# SCH_miliohn_2026-04-19.net
KiCad netlist of a schematic drawn in EasyEDA
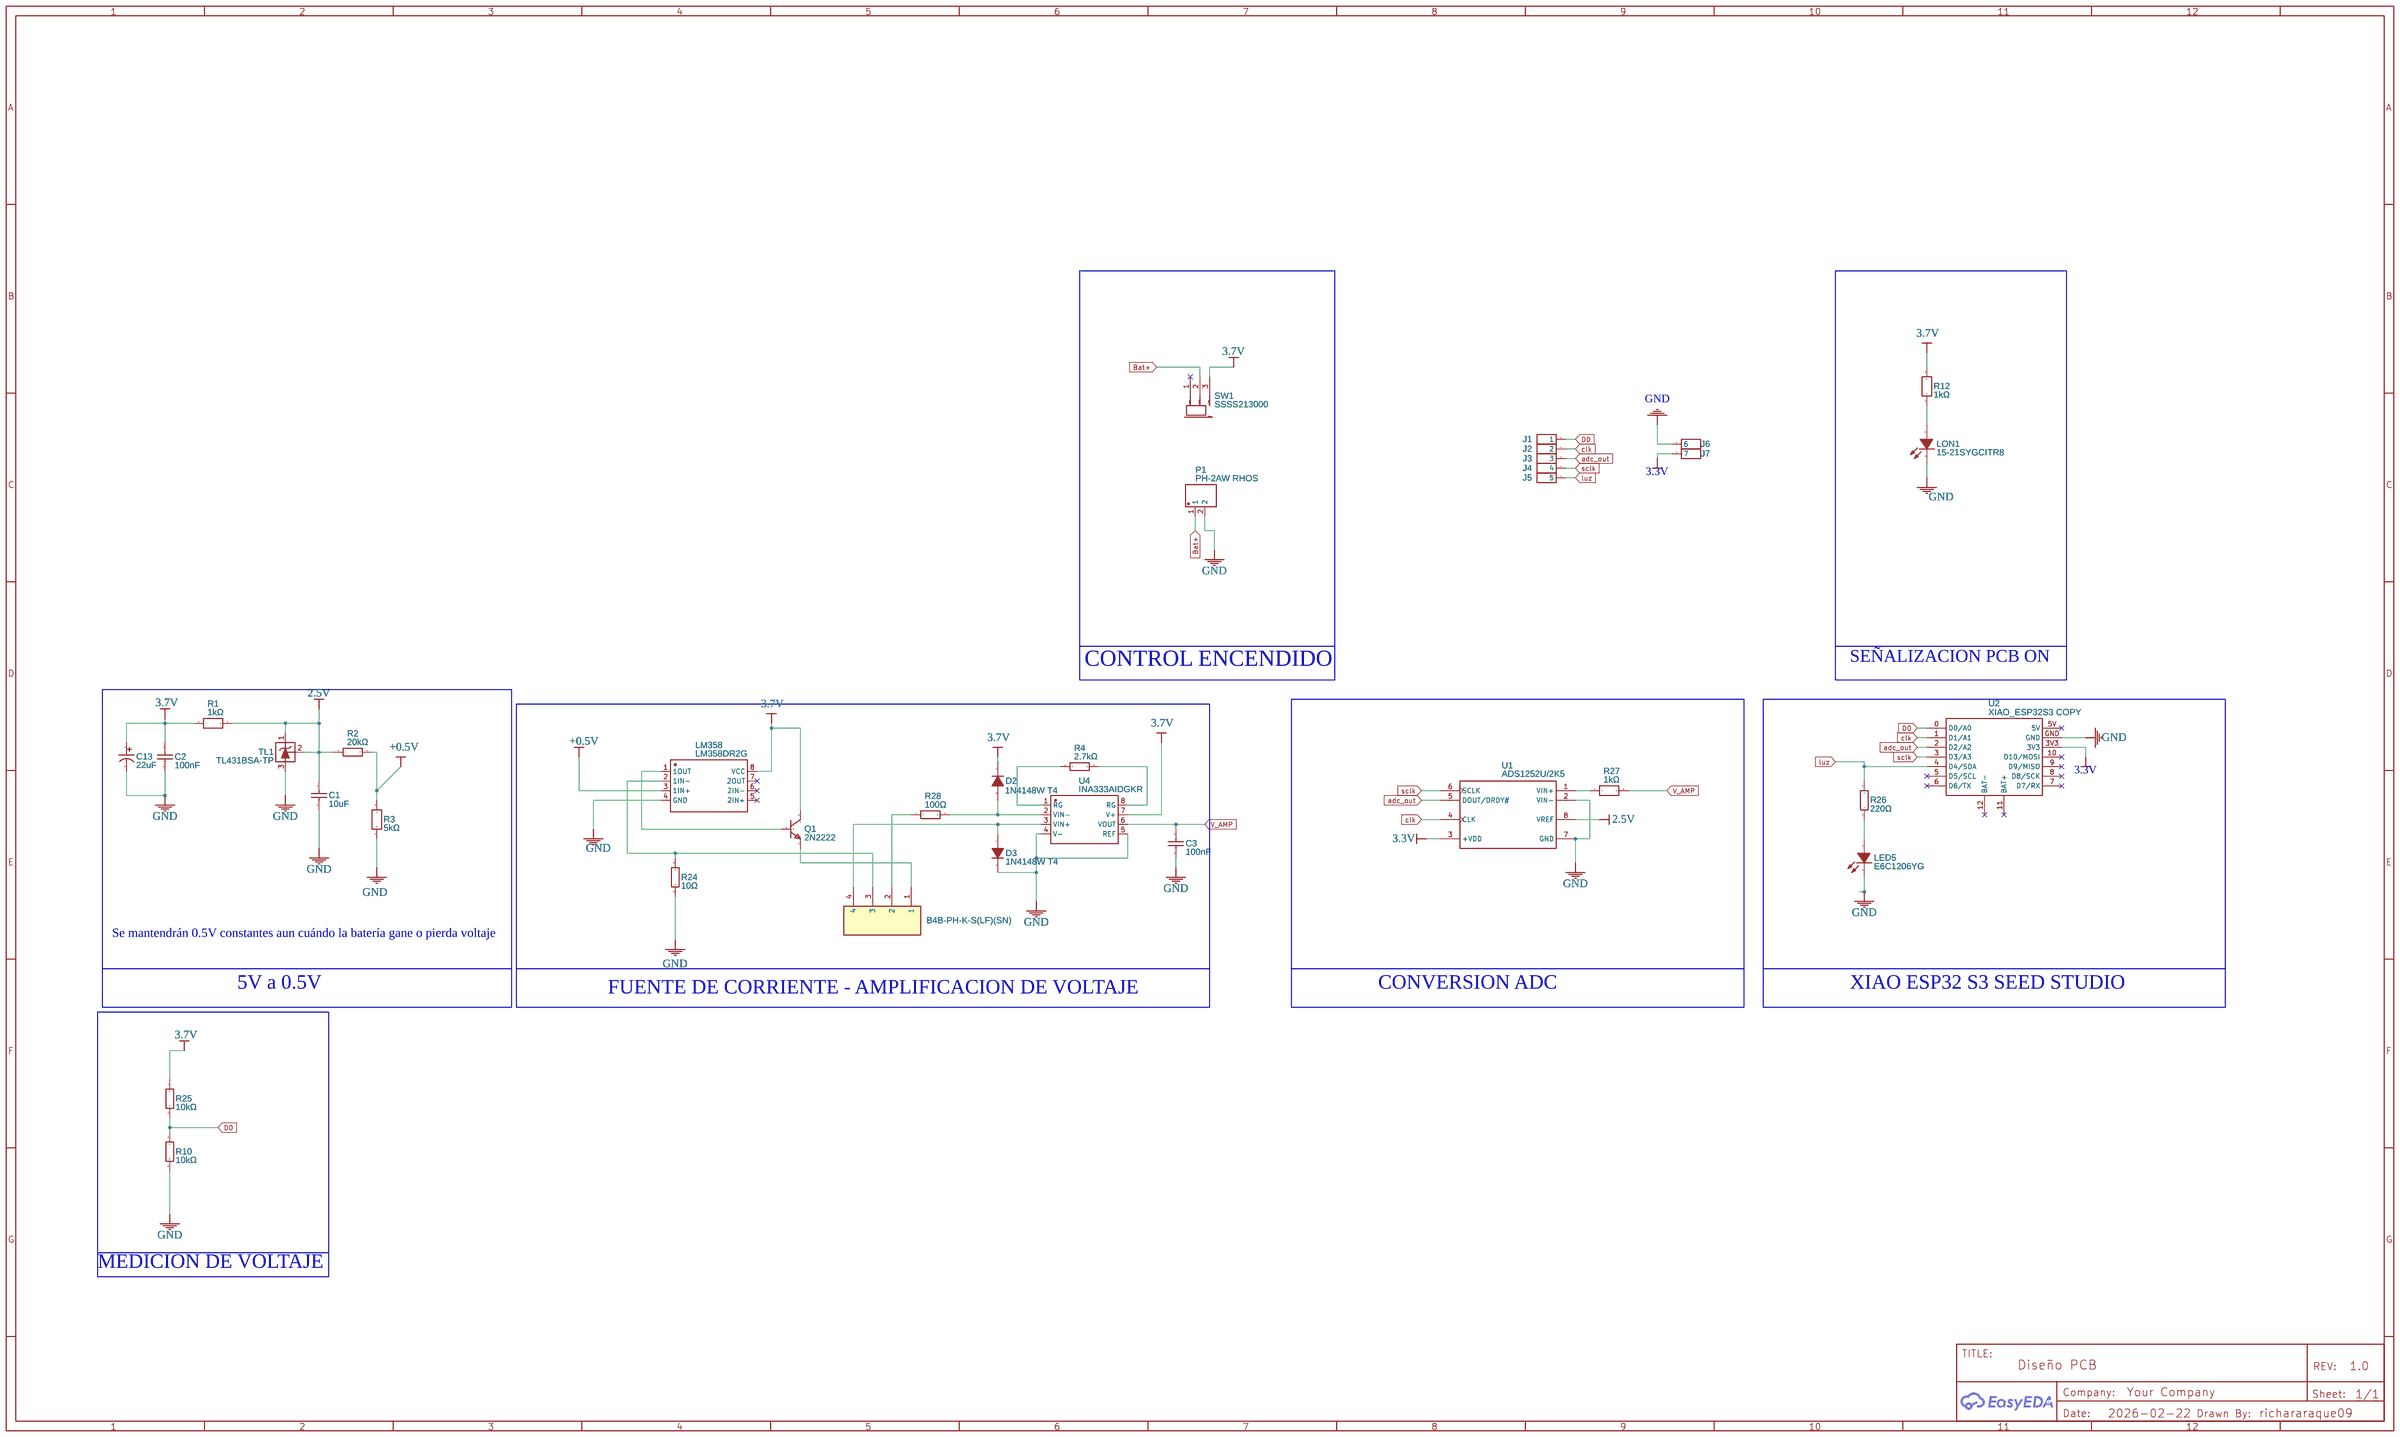
[diagram p0: schematic sheet]

(export (version "E")
  (design (tool "Eeschema 10.0.6"))
  (components
    (comp (ref "C1")
      (value "10uF")
      (fields
        (field (name "Manufacturer Part") "CL31A106KBHNNNE")
        (field (name "Manufacturer") "SAMSUNG(三星)")
      )
      (libsource (lib "") (part "CL31A106KBHNNNE"))
    )
    (comp (ref "C2")
      (value "100nF")
      (fields
        (field (name "Manufacturer Part") "CL31B104KBCNNNC")
        (field (name "Manufacturer") "SAMSUNG(三星)")
      )
      (libsource (lib "") (part "CL31B104KBCNNNC"))
    )
    (comp (ref "C3")
      (value "100nF")
      (fields
        (field (name "Manufacturer Part") "CL31B104KBCNNNC")
        (field (name "Manufacturer") "SAMSUNG(三星)")
      )
      (libsource (lib "") (part "CL31B104KBCNNNC"))
    )
    (comp (ref "C13")
      (value "22uF")
      (fields (field (name "Manufacturer Part") "RVT1C220M0405") (field (name "Manufacturer") "HONOR(荣誉)"))
      (libsource (lib "") (part "RVT1C220M0405_C3356"))
    )
    (comp (ref "D2")
      (value "1N4148W T4")
      (fields (field (name "Manufacturer Part") "1N4148W") (field (name "Manufacturer") "CJ(江苏长电/长晶)"))
      (libsource (lib "") (part "1N4148W T4"))
    )
    (comp (ref "D3")
      (value "1N4148W T4")
      (fields (field (name "Manufacturer Part") "1N4148W") (field (name "Manufacturer") "CJ(江苏长电/长晶)"))
      (libsource (lib "") (part "1N4148W T4_1"))
    )
    (comp (ref "J1") (value "HDR-M-2.54_1x1") (libsource (lib "") (part "HDR-M-2.54_1x1_4")))
    (comp (ref "J2") (value "HDR-M-2.54_1x1") (libsource (lib "") (part "HDR-M-2.54_1x1_3")))
    (comp (ref "J3") (value "HDR-M-2.54_1x1") (libsource (lib "") (part "HDR-M-2.54_1x1_2")))
    (comp (ref "J4") (value "HDR-M-2.54_1x1") (libsource (lib "") (part "HDR-M-2.54_1x1_5")))
    (comp (ref "J5") (value "HDR-M-2.54_1x1") (libsource (lib "") (part "HDR-M-2.54_1x1_1")))
    (comp (ref "J6") (value "HDR-M-2.54_1x1") (libsource (lib "") (part "HDR-M-2.54_1x1_6")))
    (comp (ref "J7") (value "HDR-M-2.54_1x1") (libsource (lib "") (part "HDR-M-2.54_1x1")))
    (comp (ref "LED5")
      (value "E6C1206YG")
      (fields (field (name "Manufacturer Part") "KT-1206YG") (field (name "Manufacturer") "KENTO"))
      (libsource (lib "") (part "E6C1206YG"))
    )
    (comp (ref "LM358")
      (value "LM358DR2G")
      (fields (field (name "Manufacturer") "onsemi(安森美)"))
      (libsource (lib "") (part "LM358DR2G"))
    )
    (comp (ref "LON1")
      (value "15-21SYGCITR8")
      (fields (field (name "Manufacturer Part") "KT-1206Y") (field (name "Manufacturer") "KENTO"))
      (libsource (lib "") (part "15-21SYGCITR8"))
    )
    (comp (ref "P1")
      (value "PH-2AW RHOS")
      (fields (field (name "Manufacturer Part") "PH-2AW") (field (name "Manufacturer") "BOOMELE(博穆精密)"))
      (libsource (lib "") (part "PH-2AW RHOS"))
    )
    (comp (ref "Q1")
      (value "2N2222")
      (fields (field (name "Manufacturer Part") "2N2222A") (field (name "Manufacturer") "ST(先科)"))
      (libsource (lib "") (part "2N2222"))
    )
    (comp (ref "R1")
      (value "1kΩ")
      (fields (field (name "Manufacturer Part") "SCR1206J1K") (field (name "Manufacturer") "VO(翔胜)"))
      (libsource (lib "") (part "SCR1206J1K"))
    )
    (comp (ref "R2")
      (value "20kΩ")
      (fields
        (field (name "Manufacturer Part") "1206W4F2002T5E")
        (field (name "Manufacturer") "UNI-ROYAL(厚声)")
      )
      (libsource (lib "") (part "1206W4F2002T5E"))
    )
    (comp (ref "R3")
      (value "5kΩ")
      (fields (field (name "Manufacturer Part") "RT1206BRD075KL") (field (name "Manufacturer") "YAGEO(国巨)"))
      (libsource (lib "") (part "RT1206BRD075KL"))
    )
    (comp (ref "R4")
      (value "2.7kΩ")
      (fields
        (field (name "Manufacturer Part") "1206W4F2701T5E")
        (field (name "Manufacturer") "UNI-ROYAL(厚声)")
      )
      (libsource (lib "") (part "1206W4F2701T5E"))
    )
    (comp (ref "R10")
      (value "10kΩ")
      (fields
        (field (name "Manufacturer Part") "1206W4F1002T5E")
        (field (name "Manufacturer") "UNI-ROYAL(厚声)")
      )
      (libsource (lib "") (part "1206W4F1002T5E"))
    )
    (comp (ref "R12")
      (value "1kΩ")
      (fields (field (name "Manufacturer Part") "SCR1206J1K") (field (name "Manufacturer") "VO(翔胜)"))
      (libsource (lib "") (part "SCR1206J1K_1"))
    )
    (comp (ref "R24")
      (value "10Ω")
      (fields (field (name "Manufacturer Part") "SG732BTTD100K") (field (name "Manufacturer") "KOA"))
      (libsource (lib "") (part "SG732BTTD100K"))
    )
    (comp (ref "R25")
      (value "10kΩ")
      (fields
        (field (name "Manufacturer Part") "1206W4F1002T5E")
        (field (name "Manufacturer") "UNI-ROYAL(厚声)")
      )
      (libsource (lib "") (part "1206W4F1002T5E"))
    )
    (comp (ref "R26")
      (value "220Ω")
      (fields
        (field (name "Manufacturer Part") "1206W4F2200T5E")
        (field (name "Manufacturer") "UNI-ROYAL(厚声)")
      )
      (libsource (lib "") (part "1206W4F2200T5E"))
    )
    (comp (ref "R27")
      (value "1kΩ")
      (fields (field (name "Manufacturer Part") "SCR1206J1K") (field (name "Manufacturer") "VO(翔胜)"))
      (libsource (lib "") (part "SCR1206J1K"))
    )
    (comp (ref "R28")
      (value "100Ω")
      (fields
        (field (name "Manufacturer Part") "0805W8F1000T5E")
        (field (name "Manufacturer") "UNI-ROYAL(厚声)")
      )
      (libsource (lib "") (part "0805W8F1000T5E"))
    )
    (comp (ref "SW1")
      (value "SSSS213000")
      (fields (field (name "Manufacturer") "ALPSALPINE(阿尔卑斯阿尔派)"))
      (libsource (lib "") (part "SSSS213000"))
    )
    (comp (ref "TEST1")
      (value "B4B-PH-K-S(LF)(SN)")
      (fields (field (name "Manufacturer") "JST"))
      (libsource (lib "") (part "B4B-PH-K-S(LF)(SN)"))
    )
    (comp (ref "TL1")
      (value "TL431BSA-TP")
      (fields (field (name "Manufacturer") "TECH PUBLIC(台舟)"))
      (libsource (lib "") (part "TL431BSA-TP"))
    )
    (comp (ref "U1")
      (value "ADS1252U/2K5")
      (fields (field (name "Manufacturer") "TI(德州仪器)"))
      (libsource (lib "") (part "ADS1252U/2K5"))
    )
    (comp (ref "U2")
      (value "XIAO_ESP32S3 COPY")
      (fields (field (name "Manufacturer Part") "XIAO ESP32S3") (field (name "Manufacturer") "SeeedStudio"))
      (libsource (lib "") (part "XIAO_ESP32S3 COPY"))
    )
    (comp (ref "U4")
      (value "INA333AIDGKR")
      (fields (field (name "Manufacturer") "TI(德州仪器)"))
      (libsource (lib "") (part "INA333AIDGKR"))
    )
  )
  (nets
    (net (code "1") (name "+0.5V") (class "Default")
      (node (ref "LM358") (pin "3") (pinfunction "1IN+_3") (pintype "unspecified"))
      (node (ref "R2") (pin "1") (pinfunction "1_1") (pintype "input"))
      (node (ref "R3") (pin "2") (pinfunction "2_2") (pintype "unspecified"))
    )
    (net (code "2") (name "2.5V") (class "Default")
      (node (ref "C1") (pin "1") (pinfunction "1_1") (pintype "input"))
      (node (ref "R1") (pin "2") (pinfunction "2_2") (pintype "unspecified"))
      (node (ref "R2") (pin "2") (pinfunction "2_2") (pintype "input"))
      (node (ref "TL1") (pin "1") (pinfunction "K_1") (pintype "unspecified"))
      (node (ref "TL1") (pin "2") (pinfunction "REF_2") (pintype "unspecified"))
      (node (ref "U1") (pin "8") (pinfunction "VREF_8") (pintype "unspecified"))
    )
    (net (code "3") (name "3.3V") (class "Default")
      (node (ref "J7") (pin "1") (pinfunction "7_1") (pintype "input"))
      (node (ref "U1") (pin "3") (pinfunction "+VDD_3") (pintype "passive"))
      (node (ref "U2") (pin "3V3") (pinfunction "3V3_3V3") (pintype "unspecified"))
    )
    (net (code "4") (name "3.7V") (class "Default")
      (node (ref "C13") (pin "1") (pinfunction "1_1") (pintype "input"))
      (node (ref "C2") (pin "1") (pinfunction "1_1") (pintype "input"))
      (node (ref "D2") (pin "1") (pinfunction "K_1") (pintype "unspecified"))
      (node (ref "LM358") (pin "8") (pinfunction "VCC_8") (pintype "unspecified"))
      (node (ref "Q1") (pin "3") (pinfunction "C_3") (pintype "unspecified"))
      (node (ref "R1") (pin "1") (pinfunction "1_1") (pintype "unspecified"))
      (node (ref "R12") (pin "2") (pinfunction "2_2") (pintype "unspecified"))
      (node (ref "R25") (pin "1") (pinfunction "1_1") (pintype "input"))
      (node (ref "SW1") (pin "3") (pinfunction "3_3") (pintype "unspecified"))
      (node (ref "U4") (pin "7") (pinfunction "V+_7") (pintype "unspecified"))
    )
    (net (code "5") (name "Bat+") (class "Default")
      (node (ref "P1") (pin "1") (pinfunction "1_1") (pintype "unspecified"))
      (node (ref "SW1") (pin "2") (pinfunction "2_2") (pintype "unspecified"))
    )
    (net (code "6") (name "D0") (class "Default")
      (node (ref "J1") (pin "1") (pinfunction "1_1") (pintype "input"))
      (node (ref "R10") (pin "1") (pinfunction "1_1") (pintype "input"))
      (node (ref "R25") (pin "2") (pinfunction "2_2") (pintype "input"))
      (node (ref "U2") (pin "0") (pinfunction "D0/A0_0") (pintype "unspecified"))
    )
    (net (code "7") (name "GND") (class "Default")
      (node (ref "C1") (pin "2") (pinfunction "2_2") (pintype "input"))
      (node (ref "C13") (pin "2") (pinfunction "2_2") (pintype "input"))
      (node (ref "C2") (pin "2") (pinfunction "2_2") (pintype "input"))
      (node (ref "C3") (pin "2") (pinfunction "2_2") (pintype "input"))
      (node (ref "D3") (pin "1") (pinfunction "K_1") (pintype "unspecified"))
      (node (ref "J6") (pin "1") (pinfunction "6_1") (pintype "input"))
      (node (ref "LED5") (pin "2") (pinfunction "-_2") (pintype "unspecified"))
      (node (ref "LM358") (pin "4") (pinfunction "GND_4") (pintype "unspecified"))
      (node (ref "LON1") (pin "1") (pinfunction "-_1") (pintype "unspecified"))
      (node (ref "P1") (pin "2") (pinfunction "2_2") (pintype "unspecified"))
      (node (ref "R10") (pin "2") (pinfunction "2_2") (pintype "input"))
      (node (ref "R24") (pin "1") (pinfunction "1_1") (pintype "unspecified"))
      (node (ref "R3") (pin "1") (pinfunction "1_1") (pintype "unspecified"))
      (node (ref "TL1") (pin "3") (pinfunction "A_3") (pintype "unspecified"))
      (node (ref "U1") (pin "2") (pinfunction "VIN-_2") (pintype "unspecified"))
      (node (ref "U1") (pin "7") (pinfunction "GND_7") (pintype "passive"))
      (node (ref "U2") (pin "GND") (pinfunction "GND_GND") (pintype "unspecified"))
      (node (ref "U4") (pin "4") (pinfunction "V-_4") (pintype "unspecified"))
      (node (ref "U4") (pin "5") (pinfunction "REF_5") (pintype "unspecified"))
    )
    (net (code "8") (name "Net-(D2-A)") (class "Default")
      (node (ref "D2") (pin "2") (pinfunction "A_2") (pintype "unspecified"))
      (node (ref "R28") (pin "2") (pinfunction "2_2") (pintype "input"))
      (node (ref "U4") (pin "2") (pinfunction "VIN-_2") (pintype "unspecified"))
    )
    (net (code "9") (name "Net-(D3-A)") (class "Default")
      (node (ref "D3") (pin "2") (pinfunction "A_2") (pintype "unspecified"))
      (node (ref "TEST1") (pin "4") (pinfunction "4_4") (pintype "input"))
      (node (ref "U4") (pin "3") (pinfunction "VIN+_3") (pintype "unspecified"))
    )
    (net (code "10") (name "Net-(LED5-+)") (class "Default")
      (node (ref "LED5") (pin "1") (pinfunction "+_1") (pintype "unspecified"))
      (node (ref "R26") (pin "1") (pinfunction "1_1") (pintype "input"))
    )
    (net (code "11") (name "Net-(LM358-1IN-)") (class "Default")
      (node (ref "LM358") (pin "2") (pinfunction "1IN-_2") (pintype "unspecified"))
      (node (ref "R24") (pin "2") (pinfunction "2_2") (pintype "unspecified"))
      (node (ref "TEST1") (pin "3") (pinfunction "3_3") (pintype "input"))
    )
    (net (code "12") (name "Net-(LM358-1OUT)") (class "Default")
      (node (ref "LM358") (pin "1") (pinfunction "1OUT_1") (pintype "unspecified"))
      (node (ref "Q1") (pin "2") (pinfunction "B_2") (pintype "unspecified"))
    )
    (net (code "13") (name "Net-(LON1-+)") (class "Default")
      (node (ref "LON1") (pin "2") (pinfunction "+_2") (pintype "unspecified"))
      (node (ref "R12") (pin "1") (pinfunction "1_1") (pintype "unspecified"))
    )
    (net (code "14") (name "Net-(Q1-E)") (class "Default")
      (node (ref "Q1") (pin "1") (pinfunction "E_1") (pintype "unspecified"))
      (node (ref "TEST1") (pin "1") (pinfunction "1_1") (pintype "input"))
    )
    (net (code "15") (name "Net-(R4-Pad1)") (class "Default")
      (node (ref "R4") (pin "1") (pinfunction "1_1") (pintype "input"))
      (node (ref "U4") (pin "1") (pinfunction "RG_1") (pintype "unspecified"))
    )
    (net (code "16") (name "Net-(R4-Pad2)") (class "Default")
      (node (ref "R4") (pin "2") (pinfunction "2_2") (pintype "input"))
      (node (ref "U4") (pin "8") (pinfunction "RG_8") (pintype "unspecified"))
    )
    (net (code "17") (name "Net-(R28-Pad1)") (class "Default")
      (node (ref "R28") (pin "1") (pinfunction "1_1") (pintype "input"))
      (node (ref "TEST1") (pin "2") (pinfunction "2_2") (pintype "input"))
    )
    (net (code "18") (name "Net-(U1-VIN+)") (class "Default")
      (node (ref "R27") (pin "1") (pinfunction "1_1") (pintype "unspecified"))
      (node (ref "U1") (pin "1") (pinfunction "VIN+_1") (pintype "unspecified"))
    )
    (net (code "19") (name "V_AMP") (class "Default")
      (node (ref "C3") (pin "1") (pinfunction "1_1") (pintype "input"))
      (node (ref "R27") (pin "2") (pinfunction "2_2") (pintype "unspecified"))
      (node (ref "U4") (pin "6") (pinfunction "VOUT_6") (pintype "unspecified"))
    )
    (net (code "20") (name "adc_out") (class "Default")
      (node (ref "J3") (pin "1") (pinfunction "3_1") (pintype "input"))
      (node (ref "U1") (pin "5") (pinfunction "DOUT/DRDY#_5") (pintype "output"))
      (node (ref "U2") (pin "2") (pinfunction "D2/A2_2") (pintype "unspecified"))
    )
    (net (code "21") (name "clk") (class "Default")
      (node (ref "J2") (pin "1") (pinfunction "2_1") (pintype "input"))
      (node (ref "U1") (pin "4") (pinfunction "CLK_4") (pintype "unspecified"))
      (node (ref "U2") (pin "1") (pinfunction "D1/A1_1") (pintype "unspecified"))
    )
    (net (code "22") (name "luz") (class "Default")
      (node (ref "J5") (pin "1") (pinfunction "5_1") (pintype "input"))
      (node (ref "R26") (pin "2") (pinfunction "2_2") (pintype "input"))
      (node (ref "U2") (pin "4") (pinfunction "D4/SDA_4") (pintype "unspecified"))
    )
    (net (code "23") (name "sclk") (class "Default")
      (node (ref "J4") (pin "1") (pinfunction "4_1") (pintype "input"))
      (node (ref "U1") (pin "6") (pinfunction "SCLK_6") (pintype "unspecified"))
      (node (ref "U2") (pin "3") (pinfunction "D3/A3_3") (pintype "unspecified"))
    )
    (net (code "24") (name "unconnected-(LM358-2IN+-Pad5)") (class "Default")
      (node (ref "LM358") (pin "5") (pinfunction "2IN+_5") (pintype "unspecified+no_connect"))
    )
    (net (code "25") (name "unconnected-(LM358-2IN--Pad6)") (class "Default")
      (node (ref "LM358") (pin "6") (pinfunction "2IN-_6") (pintype "unspecified+no_connect"))
    )
    (net (code "26") (name "unconnected-(LM358-2OUT-Pad7)") (class "Default")
      (node (ref "LM358") (pin "7") (pinfunction "2OUT_7") (pintype "unspecified+no_connect"))
    )
    (net (code "27") (name "unconnected-(SW1-Pad1)") (class "Default")
      (node (ref "SW1") (pin "1") (pinfunction "1_1") (pintype "unspecified+no_connect"))
    )
    (net (code "28") (name "unconnected-(U2-BAT+-Pad11)") (class "Default")
      (node (ref "U2") (pin "11") (pinfunction "BAT+_11") (pintype "unspecified+no_connect"))
    )
    (net (code "29") (name "unconnected-(U2-BAT--Pad12)") (class "Default")
      (node (ref "U2") (pin "12") (pinfunction "BAT-_12") (pintype "unspecified+no_connect"))
    )
    (net (code "30") (name "unconnected-(U2-D5{slash}SCL-Pad5)") (class "Default")
      (node (ref "U2") (pin "5") (pinfunction "D5/SCL_5") (pintype "unspecified+no_connect"))
    )
    (net (code "31") (name "unconnected-(U2-D6{slash}TX-Pad6)") (class "Default")
      (node (ref "U2") (pin "6") (pinfunction "D6/TX_6") (pintype "unspecified+no_connect"))
    )
    (net (code "32") (name "unconnected-(U2-D7{slash}RX-Pad7)") (class "Default")
      (node (ref "U2") (pin "7") (pinfunction "D7/RX_7") (pintype "unspecified+no_connect"))
    )
    (net (code "33") (name "unconnected-(U2-D8{slash}SCK-Pad8)") (class "Default")
      (node (ref "U2") (pin "8") (pinfunction "D8/SCK_8") (pintype "unspecified+no_connect"))
    )
    (net (code "34") (name "unconnected-(U2-D9{slash}MISO-Pad9)") (class "Default")
      (node (ref "U2") (pin "9") (pinfunction "D9/MISO_9") (pintype "unspecified+no_connect"))
    )
    (net (code "35") (name "unconnected-(U2-D10{slash}MOSI-Pad10)") (class "Default")
      (node (ref "U2") (pin "10") (pinfunction "D10/MOSI_10") (pintype "unspecified+no_connect"))
    )
    (net (code "36") (name "unconnected-(U2-Pad5V)") (class "Default")
      (node (ref "U2") (pin "5V") (pinfunction "5V_5V") (pintype "unspecified+no_connect"))
    )
  )
)
